# internet-points-signal.net
KiCad netlist of a schematic drawn in EAGLE
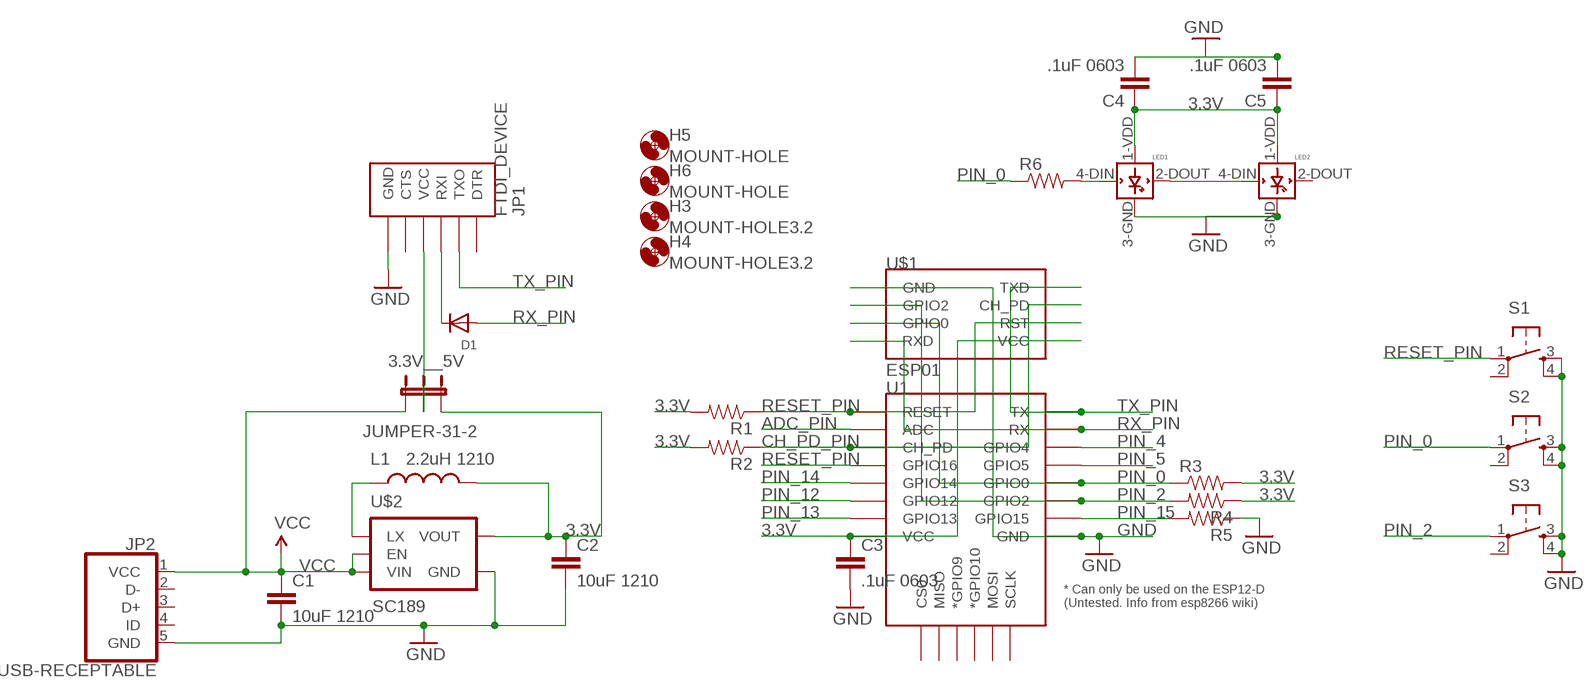
[diagram p0: schematic, sheet 1]

(export (version "E")
  (design (tool "Eeschema 10.0.6"))
  (components
    (comp (ref "3.3V__5V")
      (value "JUMPER-31-2")
      (footprint "eagle-import:SJ_3_PASTE1&2")
      (libsource (lib "eagle-import") (part "JUMPER-31-2"))
    )
    (comp (ref "C1")
      (value "10uF 1210")
      (footprint "eagle-import:1210")
      (libsource (lib "eagle-import") (part "10UF50V20%(1210)"))
    )
    (comp (ref "C2")
      (value "10uF 1210")
      (footprint "eagle-import:1210")
      (libsource (lib "eagle-import") (part "10UF50V20%(1210)"))
    )
    (comp (ref "C3")
      (value ".1uF 0603")
      (footprint "eagle-import:0603-CAP")
      (libsource (lib "eagle-import") (part "CAP0603-CAP"))
    )
    (comp (ref "C4")
      (value ".1uF 0603")
      (footprint "eagle-import:0603-CAP")
      (libsource (lib "eagle-import") (part "CAP0603-CAP"))
    )
    (comp (ref "C5")
      (value ".1uF 0603")
      (footprint "eagle-import:0603-CAP")
      (libsource (lib "eagle-import") (part "CAP0603-CAP"))
    )
    (comp (ref "D1")
      (value "DIODESOD-323F")
      (footprint "eagle-import:SOD-323F")
      (libsource (lib "eagle-import") (part "DIODESOD-323F"))
    )
    (comp (ref "H3")
      (value "MOUNT-HOLE3.2")
      (footprint "eagle-import:3,2")
      (libsource (lib "eagle-import") (part "MOUNT-HOLE3.2"))
    )
    (comp (ref "H4")
      (value "MOUNT-HOLE3.2")
      (footprint "eagle-import:3,2")
      (libsource (lib "eagle-import") (part "MOUNT-HOLE3.2"))
    )
    (comp (ref "H5")
      (value "MOUNT-HOLE")
      (footprint "eagle-import:3,2-DANGER")
      (libsource (lib "eagle-import") (part "MOUNT-HOLE"))
    )
    (comp (ref "H6")
      (value "MOUNT-HOLE")
      (footprint "eagle-import:3,2-DANGER")
      (libsource (lib "eagle-import") (part "MOUNT-HOLE"))
    )
    (comp (ref "JP1")
      (value "FTDI_DEVICE")
      (footprint "eagle-import:FTDI_DEVICE_SIDE")
      (libsource (lib "eagle-import") (part "FTDI_DEVICE"))
    )
    (comp (ref "JP2")
      (value "USB-RECEPTABLE")
      (footprint "eagle-import:FCI-10103594-0001LF")
      (libsource (lib "eagle-import") (part "USB-RECEPTABLE"))
    )
    (comp (ref "L1")
      (value "2.2uH 1210")
      (footprint "eagle-import:1210")
      (libsource (lib "eagle-import") (part "INDUCTOR1210"))
    )
    (comp (ref "LED1")
      (value "WS2812B")
      (footprint "eagle-import:WS2812B")
      (libsource (lib "eagle-import") (part "WS2812B"))
    )
    (comp (ref "LED2")
      (value "WS2812B")
      (footprint "eagle-import:WS2812B")
      (libsource (lib "eagle-import") (part "WS2812B"))
    )
    (comp (ref "R1")
      (value "RESISTOR0603-RES")
      (footprint "eagle-import:0603-RES")
      (libsource (lib "eagle-import") (part "RESISTOR0603-RES"))
    )
    (comp (ref "R2")
      (value "RESISTOR0603-RES")
      (footprint "eagle-import:0603-RES")
      (libsource (lib "eagle-import") (part "RESISTOR0603-RES"))
    )
    (comp (ref "R3")
      (value "RESISTOR0603-RES")
      (footprint "eagle-import:0603-RES")
      (libsource (lib "eagle-import") (part "RESISTOR0603-RES"))
    )
    (comp (ref "R4")
      (value "RESISTOR0603-RES")
      (footprint "eagle-import:0603-RES")
      (libsource (lib "eagle-import") (part "RESISTOR0603-RES"))
    )
    (comp (ref "R5")
      (value "RESISTOR0603-RES")
      (footprint "eagle-import:0603-RES")
      (libsource (lib "eagle-import") (part "RESISTOR0603-RES"))
    )
    (comp (ref "R6")
      (value "RESISTOR0603-RES")
      (footprint "eagle-import:0603-RES")
      (libsource (lib "eagle-import") (part "RESISTOR0603-RES"))
    )
    (comp (ref "S1")
      (value "TAC_SWITCHSMD")
      (footprint "eagle-import:TACTILE_SWITCH_SMD")
      (libsource (lib "eagle-import") (part "TAC_SWITCHSMD"))
    )
    (comp (ref "S2")
      (value "TAC_SWITCHSMD")
      (footprint "eagle-import:TACTILE_SWITCH_SMD")
      (libsource (lib "eagle-import") (part "TAC_SWITCHSMD"))
    )
    (comp (ref "S3")
      (value "TAC_SWITCHSMD")
      (footprint "eagle-import:TACTILE_SWITCH_SMD")
      (libsource (lib "eagle-import") (part "TAC_SWITCHSMD"))
    )
    (comp (ref "U$1")
      (value "ESP01")
      (footprint "eagle-import:ESP01")
      (libsource (lib "eagle-import") (part "ESP01"))
    )
    (comp (ref "U$2")
      (value "SC189")
      (footprint "eagle-import:SOT23-5")
      (libsource (lib "eagle-import") (part "SC189"))
    )
    (comp (ref "U1")
      (value "ESP12ESMD")
      (footprint "eagle-import:ESP12E-SMD")
      (libsource (lib "eagle-import") (part "ESP12ESMD"))
    )
  )
  (nets
    (net (code "1") (name "/3.3V") (class "Default")
      (node (ref "3.3V__5V") (pin "3") (pinfunction "3_3") (pintype "passive"))
      (node (ref "C2") (pin "1") (pinfunction "1_1") (pintype "passive"))
      (node (ref "C3") (pin "1") (pinfunction "1_1") (pintype "passive"))
      (node (ref "C4") (pin "1") (pinfunction "1_1") (pintype "passive"))
      (node (ref "C5") (pin "1") (pinfunction "1_1") (pintype "passive"))
      (node (ref "L1") (pin "2") (pinfunction "2_2") (pintype "passive"))
      (node (ref "LED1") (pin "1-VDD") (pinfunction "VDD_1-VDD") (pintype "bidirectional"))
      (node (ref "LED2") (pin "1-VDD") (pinfunction "VDD_1-VDD") (pintype "bidirectional"))
      (node (ref "R1") (pin "2") (pinfunction "2_2") (pintype "passive"))
      (node (ref "R2") (pin "2") (pinfunction "2_2") (pintype "passive"))
      (node (ref "R3") (pin "2") (pinfunction "2_2") (pintype "passive"))
      (node (ref "R4") (pin "1") (pinfunction "1_1") (pintype "passive"))
      (node (ref "U$1") (pin "VCC") (pinfunction "VCC_VCC") (pintype "bidirectional"))
      (node (ref "U$2") (pin "4") (pinfunction "VOUT_4") (pintype "input"))
      (node (ref "U1") (pin "VCC") (pinfunction "VCC_VCC") (pintype "bidirectional"))
    )
    (net (code "2") (name "/ADC_PIN") (class "Default")
      (node (ref "U1") (pin "ADC") (pinfunction "ADC_ADC") (pintype "bidirectional"))
    )
    (net (code "3") (name "/CH_PD_PIN") (class "Default")
      (node (ref "R2") (pin "1") (pinfunction "1_1") (pintype "passive"))
      (node (ref "U$1") (pin "CH_PD") (pinfunction "CH_PD_CH_PD") (pintype "bidirectional"))
      (node (ref "U1") (pin "CH_PD") (pinfunction "CH_PD_CH_PD") (pintype "bidirectional"))
    )
    (net (code "4") (name "/PIN_0") (class "Default")
      (node (ref "R3") (pin "1") (pinfunction "1_1") (pintype "passive"))
      (node (ref "R6") (pin "1") (pinfunction "1_1") (pintype "passive"))
      (node (ref "S2") (pin "1") (pinfunction "1_1") (pintype "passive"))
      (node (ref "U$1") (pin "GPIO0") (pinfunction "GPIO0_GPIO0") (pintype "bidirectional"))
      (node (ref "U1") (pin "GPIO0") (pinfunction "GPIO0_GPIO0") (pintype "bidirectional"))
    )
    (net (code "5") (name "/PIN_2") (class "Default")
      (node (ref "R4") (pin "2") (pinfunction "2_2") (pintype "passive"))
      (node (ref "S3") (pin "1") (pinfunction "1_1") (pintype "passive"))
      (node (ref "U$1") (pin "GPIO2") (pinfunction "GPIO2_GPIO2") (pintype "bidirectional"))
      (node (ref "U1") (pin "GPIO2") (pinfunction "GPIO2_GPIO2") (pintype "bidirectional"))
    )
    (net (code "6") (name "/PIN_4") (class "Default")
      (node (ref "U1") (pin "GPIO4") (pinfunction "GPIO4_GPIO4") (pintype "bidirectional"))
    )
    (net (code "7") (name "/PIN_5") (class "Default")
      (node (ref "U1") (pin "GPIO5") (pinfunction "GPIO5_GPIO5") (pintype "bidirectional"))
    )
    (net (code "8") (name "/PIN_12") (class "Default")
      (node (ref "U1") (pin "GPIO12") (pinfunction "GPIO12_GPIO12") (pintype "bidirectional"))
    )
    (net (code "9") (name "/PIN_13") (class "Default")
      (node (ref "U1") (pin "GPIO13") (pinfunction "GPIO13_GPIO13") (pintype "bidirectional"))
    )
    (net (code "10") (name "/PIN_14") (class "Default")
      (node (ref "U1") (pin "GPIO14") (pinfunction "GPIO14_GPIO14") (pintype "bidirectional"))
    )
    (net (code "11") (name "/PIN_15") (class "Default")
      (node (ref "R5") (pin "2") (pinfunction "2_2") (pintype "passive"))
      (node (ref "U1") (pin "GPIO15") (pinfunction "GPIO15_GPIO15") (pintype "bidirectional"))
    )
    (net (code "12") (name "/RESET_PIN") (class "Default")
      (node (ref "R1") (pin "1") (pinfunction "1_1") (pintype "passive"))
      (node (ref "S1") (pin "1") (pinfunction "1_1") (pintype "passive"))
      (node (ref "U$1") (pin "RST") (pinfunction "RST_RST") (pintype "bidirectional"))
      (node (ref "U1") (pin "GPIO16") (pinfunction "GPIO16_GPIO16") (pintype "bidirectional"))
      (node (ref "U1") (pin "RESET") (pinfunction "RESET_RESET") (pintype "bidirectional"))
    )
    (net (code "13") (name "/RX_PIN") (class "Default")
      (node (ref "D1") (pin "A") (pinfunction "A_A") (pintype "passive"))
      (node (ref "U$1") (pin "RX") (pinfunction "RXD_RX") (pintype "bidirectional"))
      (node (ref "U1") (pin "RXD0") (pinfunction "RX_RXD0") (pintype "bidirectional"))
    )
    (net (code "14") (name "/TX_PIN") (class "Default")
      (node (ref "JP1") (pin "P$2") (pinfunction "TXO_P$2") (pintype "bidirectional"))
      (node (ref "U$1") (pin "TX") (pinfunction "TXD_TX") (pintype "bidirectional"))
      (node (ref "U1") (pin "TXD0") (pinfunction "TX_TXD0") (pintype "bidirectional"))
    )
    (net (code "15") (name "GND") (class "Default")
      (node (ref "C1") (pin "2") (pinfunction "2_2") (pintype "passive"))
      (node (ref "C2") (pin "2") (pinfunction "2_2") (pintype "passive"))
      (node (ref "C3") (pin "2") (pinfunction "2_2") (pintype "passive"))
      (node (ref "C4") (pin "2") (pinfunction "2_2") (pintype "passive"))
      (node (ref "C5") (pin "2") (pinfunction "2_2") (pintype "passive"))
      (node (ref "JP1") (pin "P$6") (pinfunction "GND_P$6") (pintype "bidirectional"))
      (node (ref "JP2") (pin "5") (pinfunction "GND_5") (pintype "bidirectional"))
      (node (ref "LED1") (pin "3-GND") (pinfunction "GND_3-GND") (pintype "bidirectional"))
      (node (ref "LED2") (pin "3-GND") (pinfunction "GND_3-GND") (pintype "bidirectional"))
      (node (ref "R5") (pin "1") (pinfunction "1_1") (pintype "passive"))
      (node (ref "S1") (pin "3") (pinfunction "3_3") (pintype "passive"))
      (node (ref "S1") (pin "4") (pinfunction "4_4") (pintype "passive"))
      (node (ref "S2") (pin "3") (pinfunction "3_3") (pintype "passive"))
      (node (ref "S2") (pin "4") (pinfunction "4_4") (pintype "passive"))
      (node (ref "S3") (pin "3") (pinfunction "3_3") (pintype "passive"))
      (node (ref "S3") (pin "4") (pinfunction "4_4") (pintype "passive"))
      (node (ref "U$1") (pin "GND") (pinfunction "GND_GND") (pintype "bidirectional"))
      (node (ref "U$2") (pin "2") (pinfunction "GND_2") (pintype "input"))
      (node (ref "U1") (pin "GND") (pinfunction "GND_GND") (pintype "bidirectional"))
    )
    (net (code "16") (name "Net-(JP1-RXI)") (class "Default")
      (node (ref "D1") (pin "C") (pinfunction "C_C") (pintype "passive"))
      (node (ref "JP1") (pin "P$3") (pinfunction "RXI_P$3") (pintype "bidirectional"))
    )
    (net (code "17") (name "Net-(JP1-VCC)") (class "Default")
      (node (ref "3.3V__5V") (pin "2") (pinfunction "2_2") (pintype "passive"))
      (node (ref "JP1") (pin "P$4") (pinfunction "VCC_P$4") (pintype "bidirectional"))
    )
    (net (code "18") (name "Net-(LED1-DIN)") (class "Default")
      (node (ref "LED1") (pin "4-DIN") (pinfunction "DIN_4-DIN") (pintype "input"))
      (node (ref "R6") (pin "2") (pinfunction "2_2") (pintype "passive"))
    )
    (net (code "19") (name "Net-(LED1-DOUT)") (class "Default")
      (node (ref "LED1") (pin "2-DOUT") (pinfunction "DOUT_2-DOUT") (pintype "output"))
      (node (ref "LED2") (pin "4-DIN") (pinfunction "DIN_4-DIN") (pintype "input"))
    )
    (net (code "20") (name "Net-(U$2-LX)") (class "Default")
      (node (ref "L1") (pin "1") (pinfunction "1_1") (pintype "passive"))
      (node (ref "U$2") (pin "5") (pinfunction "LX_5") (pintype "input"))
    )
    (net (code "21") (name "VCC") (class "Default")
      (node (ref "3.3V__5V") (pin "1") (pinfunction "1_1") (pintype "passive"))
      (node (ref "C1") (pin "1") (pinfunction "1_1") (pintype "passive"))
      (node (ref "JP2") (pin "1") (pinfunction "VCC_1") (pintype "bidirectional"))
      (node (ref "U$2") (pin "1") (pinfunction "VIN_1") (pintype "input"))
      (node (ref "U$2") (pin "3") (pinfunction "EN_3") (pintype "passive"))
    )
    (net (code "22") (name "unconnected-(JP1-CTS-PadP$5)") (class "Default")
      (node (ref "JP1") (pin "P$5") (pinfunction "CTS_P$5") (pintype "bidirectional"))
    )
    (net (code "23") (name "unconnected-(JP1-DTR-PadP$1)") (class "Default")
      (node (ref "JP1") (pin "P$1") (pinfunction "DTR_P$1") (pintype "bidirectional"))
    )
    (net (code "24") (name "unconnected-(JP2-D+-Pad3)") (class "Default")
      (node (ref "JP2") (pin "3") (pinfunction "D+_3") (pintype "bidirectional"))
    )
    (net (code "25") (name "unconnected-(JP2-D--Pad2)") (class "Default")
      (node (ref "JP2") (pin "2") (pinfunction "D-_2") (pintype "bidirectional"))
    )
    (net (code "26") (name "unconnected-(JP2-ID-Pad4)") (class "Default")
      (node (ref "JP2") (pin "4") (pinfunction "ID_4") (pintype "bidirectional"))
    )
    (net (code "27") (name "unconnected-(LED2-DOUT-Pad2-DOUT)") (class "Default")
      (node (ref "LED2") (pin "2-DOUT") (pinfunction "DOUT_2-DOUT") (pintype "output"))
    )
    (net (code "28") (name "unconnected-(S1-Pad2)") (class "Default")
      (node (ref "S1") (pin "2") (pinfunction "2_2") (pintype "passive"))
    )
    (net (code "29") (name "unconnected-(S2-Pad2)") (class "Default")
      (node (ref "S2") (pin "2") (pinfunction "2_2") (pintype "passive"))
    )
    (net (code "30") (name "unconnected-(S3-Pad2)") (class "Default")
      (node (ref "S3") (pin "2") (pinfunction "2_2") (pintype "passive"))
    )
    (net (code "31") (name "unconnected-(U1-*GPIO9-PadGPIO9)") (class "Default")
      (node (ref "U1") (pin "GPIO9") (pinfunction "*GPIO9_GPIO9") (pintype "bidirectional"))
    )
    (net (code "32") (name "unconnected-(U1-*GPIO10-PadGPIO10)") (class "Default")
      (node (ref "U1") (pin "GPIO10") (pinfunction "*GPIO10_GPIO10") (pintype "bidirectional"))
    )
    (net (code "33") (name "unconnected-(U1-PadCS0)") (class "Default")
      (node (ref "U1") (pin "CS0") (pinfunction "CS0_CS0") (pintype "bidirectional"))
    )
    (net (code "34") (name "unconnected-(U1-PadMISO)") (class "Default")
      (node (ref "U1") (pin "MISO") (pinfunction "MISO_MISO") (pintype "bidirectional"))
    )
    (net (code "35") (name "unconnected-(U1-PadMOSI)") (class "Default")
      (node (ref "U1") (pin "MOSI") (pinfunction "MOSI_MOSI") (pintype "bidirectional"))
    )
    (net (code "36") (name "unconnected-(U1-PadSCLK)") (class "Default")
      (node (ref "U1") (pin "SCLK") (pinfunction "SCLK_SCLK") (pintype "bidirectional"))
    )
  )
)
